# Zio_Qwiic_UV_Sensor_VEML6075.net
KiCad netlist of a schematic drawn in EAGLE
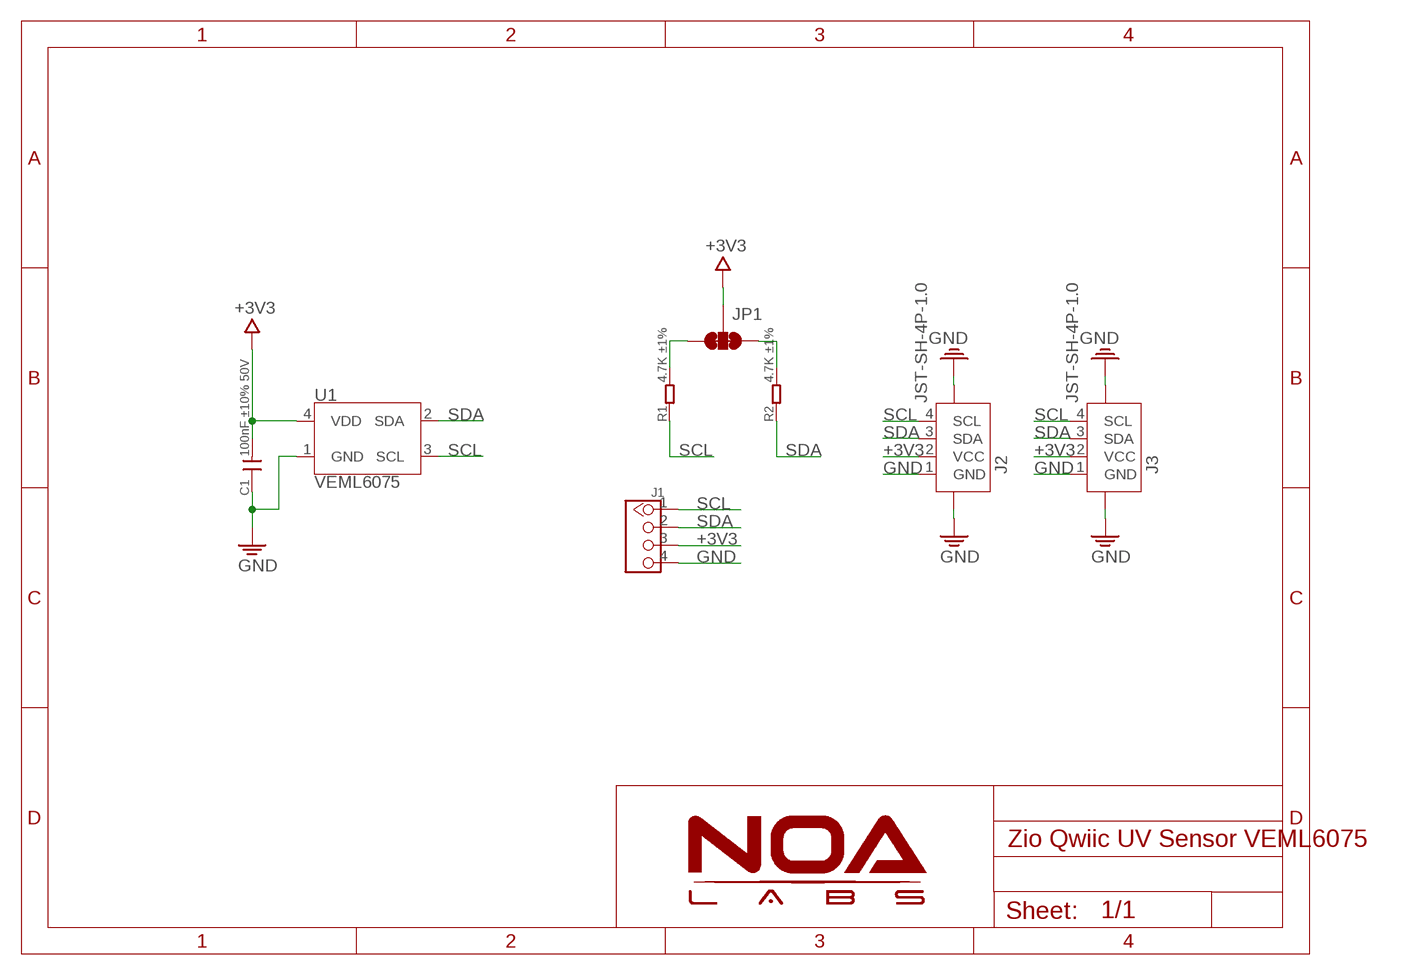
[diagram p0: schematic, sheet 1]

(export (version "E")
  (design (tool "Eeschema 10.0.6"))
  (components
    (comp (ref "C1")
      (value "100nF ±10% 50V")
      (footprint "eagle-import:C0603")
      (libsource (lib "eagle-import") (part "C-0603"))
    )
    (comp (ref "J1")
      (value "HEADER-4P-60/35MIL")
      (footprint "eagle-import:4P-65_35MIL")
      (libsource (lib "eagle-import") (part "HEADER-4P-60/35MIL"))
    )
    (comp (ref "J2")
      (value "JST-SH-4P-1.0")
      (footprint "eagle-import:JST-SH-4P")
      (libsource (lib "eagle-import") (part "JST-SH-4P-1.0"))
    )
    (comp (ref "J3")
      (value "JST-SH-4P-1.0")
      (footprint "eagle-import:JST-SH-4P")
      (libsource (lib "eagle-import") (part "JST-SH-4P-1.0"))
    )
    (comp (ref "JP1")
      (value "SMT-JUMPER_3_2-NC_TRACE")
      (footprint "eagle-import:SMT-JUMPER_3_2-NC_TRACE")
      (libsource (lib "eagle-import") (part "SMT-JUMPER_3_2-NC_TRACE"))
    )
    (comp (ref "R1")
      (value "4.7K ±1%")
      (footprint "eagle-import:R0603")
      (libsource (lib "eagle-import") (part "R-0603"))
    )
    (comp (ref "R2")
      (value "4.7K ±1%")
      (footprint "eagle-import:R0603")
      (libsource (lib "eagle-import") (part "R-0603"))
    )
    (comp (ref "U1")
      (value "VEML6075")
      (footprint "eagle-import:VEML6075_A3OP")
      (libsource (lib "eagle-import") (part "VEML6075"))
    )
  )
  (nets
    (net (code "1") (name "+3V3") (class "Default")
      (node (ref "C1") (pin "2") (pinfunction "2_2") (pintype "passive"))
      (node (ref "J1") (pin "3") (pinfunction "P$3_3") (pintype "bidirectional"))
      (node (ref "J2") (pin "2") (pinfunction "VCC_2") (pintype "bidirectional"))
      (node (ref "J3") (pin "2") (pinfunction "VCC_2") (pintype "bidirectional"))
      (node (ref "JP1") (pin "2") (pinfunction "2_2") (pintype "passive"))
      (node (ref "U1") (pin "4") (pinfunction "VDD_4") (pintype "bidirectional"))
    )
    (net (code "2") (name "/SCL") (class "Default")
      (node (ref "J1") (pin "1") (pinfunction "P$1_1") (pintype "bidirectional"))
      (node (ref "J2") (pin "4") (pinfunction "SCL_4") (pintype "bidirectional"))
      (node (ref "J3") (pin "4") (pinfunction "SCL_4") (pintype "bidirectional"))
      (node (ref "R1") (pin "1") (pinfunction "1_1") (pintype "passive"))
      (node (ref "U1") (pin "3") (pinfunction "SCL_3") (pintype "bidirectional"))
    )
    (net (code "3") (name "/SDA") (class "Default")
      (node (ref "J1") (pin "2") (pinfunction "P$2_2") (pintype "bidirectional"))
      (node (ref "J2") (pin "3") (pinfunction "SDA_3") (pintype "bidirectional"))
      (node (ref "J3") (pin "3") (pinfunction "SDA_3") (pintype "bidirectional"))
      (node (ref "R2") (pin "1") (pinfunction "1_1") (pintype "passive"))
      (node (ref "U1") (pin "2") (pinfunction "SDA_2") (pintype "bidirectional"))
    )
    (net (code "4") (name "GND") (class "Default")
      (node (ref "C1") (pin "1") (pinfunction "1_1") (pintype "passive"))
      (node (ref "J1") (pin "4") (pinfunction "P$4_4") (pintype "bidirectional"))
      (node (ref "J2") (pin "1") (pinfunction "GND_1") (pintype "bidirectional"))
      (node (ref "J2") (pin "NC1") (pinfunction "5_NC1") (pintype "bidirectional"))
      (node (ref "J2") (pin "NC2") (pinfunction "6_NC2") (pintype "bidirectional"))
      (node (ref "J3") (pin "1") (pinfunction "GND_1") (pintype "bidirectional"))
      (node (ref "J3") (pin "NC1") (pinfunction "5_NC1") (pintype "bidirectional"))
      (node (ref "J3") (pin "NC2") (pinfunction "6_NC2") (pintype "bidirectional"))
      (node (ref "U1") (pin "1") (pinfunction "GND_1") (pintype "bidirectional"))
    )
    (net (code "5") (name "Net-(JP1-Pad1)") (class "Default")
      (node (ref "JP1") (pin "1") (pinfunction "1_1") (pintype "passive"))
      (node (ref "R2") (pin "2") (pinfunction "2_2") (pintype "passive"))
    )
    (net (code "6") (name "Net-(JP1-Pad3)") (class "Default")
      (node (ref "JP1") (pin "3") (pinfunction "3_3") (pintype "passive"))
      (node (ref "R1") (pin "2") (pinfunction "2_2") (pintype "passive"))
    )
  )
)
